# 3_BLE-T1-mcu.net
KiCad netlist of a schematic drawn in Altium Designer
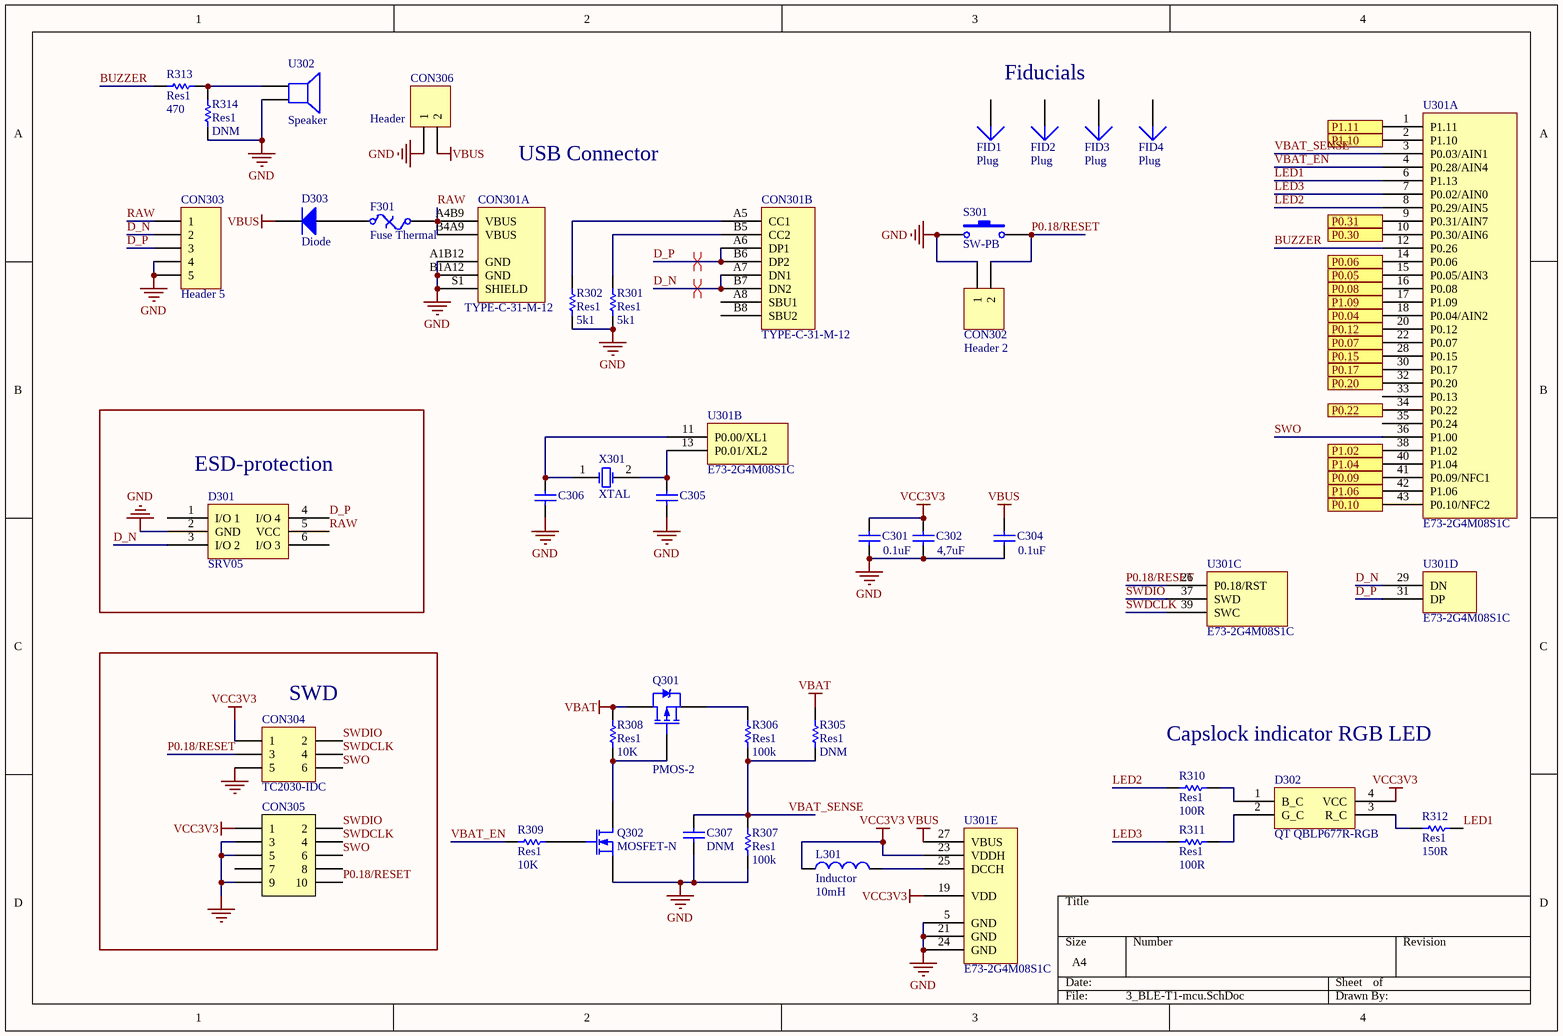
[diagram p0: 3_BLE-T1-mcu.SchDoc]

(export (version "E")
  (design (tool "Eeschema 10.0.6"))
  (components
    (comp (ref "C301")
      (value "0.1uF")
      (footprint "C0603[1608]")
      (description "Capacitor")
      (fields (field (name "MFG") "KEMET") (field (name "LCSC PART #") "C14663"))
      (libsource (lib "Miscellaneous Devices") (part "Cap"))
    )
    (comp (ref "C302")
      (value "4,7uF")
      (footprint "C0603[1608]")
      (description "Capacitor")
      (fields (field (name "LCSC PART #") "C19666") (field (name "MRF.PART") "CL10A475KO8NNNC"))
      (libsource (lib "Miscellaneous Devices") (part "Cap"))
    )
    (comp (ref "C304")
      (value "0.1uF")
      (footprint "C0603[1608]")
      (description "Capacitor")
      (fields (field (name "MFG") "KEMET") (field (name "LCSC PART #") "C14663"))
      (libsource (lib "Miscellaneous Devices") (part "Cap"))
    )
    (comp (ref "C305")
      (value "~")
      (footprint "C0603[1608]")
      (description "Capacitor")
      (libsource (lib "Miscellaneous Devices") (part "Cap"))
    )
    (comp (ref "C306")
      (value "~")
      (footprint "C0603[1608]")
      (description "Capacitor")
      (libsource (lib "Miscellaneous Devices") (part "Cap"))
    )
    (comp (ref "C307")
      (value "DNM")
      (footprint "C0603[1608]")
      (description "Capacitor")
      (libsource (lib "Miscellaneous Devices") (part "Cap"))
    )
    (comp (ref "CON301")
      (value "TYPE-C-31-M-12")
      (footprint "TYPE-C-31-M-12")
      (fields (field (name "MFG") "Korean Hroparts Elec") (field (name "LCSC PART #") "C165948"))
      (libsource (lib "Schlib1") (part "TYPE-C-31-M-12"))
    )
    (comp (ref "CON302")
      (value "Header 2")
      (footprint "HDR1X2")
      (description "Header, 2-Pin")
      (libsource (lib "") (part "Header 2_1"))
    )
    (comp (ref "CON303")
      (value "Header 5")
      (footprint "JST SM04B-SRSS-TB")
      (description "JST for USB daughter board")
      (fields (field (name "MFG") "JST Sales America Inc.") (field (name "LCSC PART #") "C160404"))
      (libsource (lib "Miscellaneous Connectors") (part "Header 5"))
    )
    (comp (ref "CON304")
      (value "TC2030-IDC")
      (footprint "TC2030-IDC-NL")
      (description "Header, 3-Pin, Dual row")
      (libsource (lib "Miscellaneous Connectors") (part "Header 3X2"))
    )
    (comp (ref "CON305")
      (value "~")
      (footprint "HDR_2x5-SMD-1.27mm-K")
      (description "Pin Header 2x5, 1.27mm (50mil), SMD, Keying Shroud")
      (fields (field (name "MFG") "Samtec Inc."))
      (libsource (lib "Nordic Passive DB") (part "CONN-2x5"))
    )
    (comp (ref "CON306")
      (value "Header")
      (footprint "HDR1X2")
      (description "Header, 2-Pin")
      (libsource (lib "Miscellaneous Connectors") (part "Header 2"))
    )
    (comp (ref "D301")
      (value "SRV05")
      (footprint "SOT-23-6")
      (fields (field (name "LCSC PART #") "C85364") (field (name "MRF.PART") "SRV05-4-P-T7"))
      (libsource (lib "Keebs") (part "SRV05"))
    )
    (comp (ref "D302")
      (value "QT QBLP677R-RGB")
      (footprint "QT QBLP677R-RGB")
      (description "RGB LED")
      (fields (field (name "MFG") "QT Brightek (QTB)"))
      (libsource (lib "Keebs") (part "QT QBLP677R-RGB"))
    )
    (comp (ref "D303")
      (value "Diode")
      (footprint "SOD-123")
      (description "Default Diode")
      (fields (field (name "LCSC PART #") "C8598") (field (name "MRF.PART") "B5819W"))
      (libsource (lib "Miscellaneous Devices") (part "Diode"))
    )
    (comp (ref "F301")
      (value "Fuse Thermal")
      (footprint "C1206[3216]")
      (description "Thermal Fuse")
      (fields (field (name "MFG") "Bel Fuse Inc.") (field (name "LCSC PART #") "C135338"))
      (libsource (lib "Miscellaneous Devices") (part "Fuse Thermal"))
    )
    (comp (ref "FID1")
      (value "Plug")
      (footprint "Fiducial_Nordic")
      (libsource (lib "Miscellaneous Connectors") (part "Plug"))
    )
    (comp (ref "FID2")
      (value "Plug")
      (footprint "Fiducial_Nordic")
      (libsource (lib "Miscellaneous Connectors") (part "Plug"))
    )
    (comp (ref "FID3")
      (value "Plug")
      (footprint "Fiducial_Nordic")
      (libsource (lib "Miscellaneous Connectors") (part "Plug"))
    )
    (comp (ref "FID4")
      (value "Plug")
      (footprint "Fiducial_Nordic")
      (libsource (lib "Miscellaneous Connectors") (part "Plug"))
    )
    (comp (ref "L301")
      (value "Inductor")
      (footprint "C0603[1608]")
      (fields (field (name "ALTIUM_VALUE") "10mH"))
      (libsource (lib "Miscellaneous Devices") (part "Inductor"))
    )
    (comp (ref "Q301")
      (value "PMOS-2")
      (footprint "SOT-23-3")
      (description "P-Channel Power MOSFET")
      (fields (field (name "MRF.PART") "SI2301CDS-T1-GE3") (field (name "LCSC PART #") "C10487"))
      (libsource (lib "Miscellaneous Devices") (part "PMOS-2"))
    )
    (comp (ref "Q302")
      (value "MOSFET-N")
      (footprint "SOT-23-3")
      (description "N-Channel MOSFET")
      (fields (field (name "LCSC PART #") "C8545") (field (name "MRF.PART") "2N7002"))
      (libsource (lib "Miscellaneous Devices") (part "MOSFET-N"))
    )
    (comp (ref "R301")
      (value "Res1")
      (footprint "R0603[1608]")
      (description "Resistor")
      (fields
        (field (name "ALTIUM_VALUE") "5k1")
        (field (name "LCSC PART #") "C23186")
        (field (name "MRF.PART") "0603WAF5101T5E")
      )
      (libsource (lib "Miscellaneous Devices") (part "Res1"))
    )
    (comp (ref "R302")
      (value "Res1")
      (footprint "R0603[1608]")
      (description "Resistor")
      (fields
        (field (name "ALTIUM_VALUE") "5k1")
        (field (name "LCSC PART #") "C23186")
        (field (name "MRF.PART") "0603WAF5101T5E")
      )
      (libsource (lib "Miscellaneous Devices") (part "Res1"))
    )
    (comp (ref "R305")
      (value "Res1")
      (footprint "R0603[1608]")
      (description "Resistor")
      (fields (field (name "ALTIUM_VALUE") "DNM"))
      (libsource (lib "Miscellaneous Devices") (part "Res1"))
    )
    (comp (ref "R306")
      (value "Res1")
      (footprint "R0603[1608]")
      (description "Resistor")
      (fields
        (field (name "ALTIUM_VALUE") "100k")
        (field (name "MRF.PART") "0603WAF1003T5E")
        (field (name "LCSC PART #") "C25803")
      )
      (libsource (lib "Miscellaneous Devices") (part "Res1"))
    )
    (comp (ref "R307")
      (value "Res1")
      (footprint "R0603[1608]")
      (description "Resistor")
      (fields
        (field (name "ALTIUM_VALUE") "100k")
        (field (name "MRF.PART") "0603WAF1003T5E")
        (field (name "LCSC PART #") "C25803")
      )
      (libsource (lib "Miscellaneous Devices") (part "Res1"))
    )
    (comp (ref "R308")
      (value "Res1")
      (footprint "R0603[1608]")
      (description "Resistor")
      (fields (field (name "ALTIUM_VALUE") "10K"))
      (libsource (lib "Miscellaneous Devices") (part "Res1"))
    )
    (comp (ref "R309")
      (value "Res1")
      (footprint "R0603[1608]")
      (description "Resistor")
      (fields (field (name "ALTIUM_VALUE") "10K"))
      (libsource (lib "Miscellaneous Devices") (part "Res1"))
    )
    (comp (ref "R310")
      (value "Res1")
      (footprint "R0603[1608]")
      (description "Resistor")
      (fields
        (field (name "ALTIUM_VALUE") "100R")
        (field (name "LCSC PART #") "C22775")
        (field (name "MRF.PART") "0603WAF1000T5E")
      )
      (libsource (lib "Miscellaneous Devices") (part "Res1"))
    )
    (comp (ref "R311")
      (value "Res1")
      (footprint "R0603[1608]")
      (description "Resistor")
      (fields
        (field (name "ALTIUM_VALUE") "100R")
        (field (name "LCSC PART #") "C22775")
        (field (name "MRF.PART") "0603WAF1000T5E")
      )
      (libsource (lib "Miscellaneous Devices") (part "Res1"))
    )
    (comp (ref "R312")
      (value "Res1")
      (footprint "R0603[1608]")
      (description "Resistor")
      (fields
        (field (name "ALTIUM_VALUE") "150R")
        (field (name "LCSC PART #") "C22808")
        (field (name "MRF.PART") "0603WAF1500T5E")
      )
      (libsource (lib "Miscellaneous Devices") (part "Res1"))
    )
    (comp (ref "R313")
      (value "Res1")
      (footprint "R0603[1608]")
      (description "Resistor")
      (fields
        (field (name "ALTIUM_VALUE") "470")
        (field (name "MFG") "Panasonic Electronic Components")
        (field (name "LCSC PART #") "C23179")
      )
      (libsource (lib "Miscellaneous Devices") (part "Res1"))
    )
    (comp (ref "R314")
      (value "Res1")
      (footprint "R0603[1608]")
      (description "Resistor")
      (fields
        (field (name "ALTIUM_VALUE") "DNM")
        (field (name "LCSC PART #") "C23345")
        (field (name "MRF.PART") "0603WAF220JT5E")
      )
      (libsource (lib "Miscellaneous Devices") (part "Res1"))
    )
    (comp (ref "S301")
      (value "SW-PB")
      (footprint "Combo switch")
      (description "Switch")
      (fields (field (name "MFG") "C&K") (field (name "MRF.PART") "TS-1187A-C-D-B"))
      (libsource (lib "Miscellaneous Devices") (part "SW-PB"))
    )
    (comp (ref "U301")
      (value "E73-2G4M08S1C")
      (footprint "E73-2G4M08S1C BLE-T1")
      (libsource (lib "Keebs") (part "E73-2G4M08S1C"))
    )
    (comp (ref "U302")
      (value "Speaker")
      (footprint "buzzer 12x12")
      (description "Loudspeaker")
      (libsource (lib "Miscellaneous Devices") (part "Speaker"))
    )
    (comp (ref "X301")
      (value "XTAL")
      (footprint "Seiko Epson Q13FC1350000400")
      (description "Crystal Oscillator")
      (fields (field (name "LCSC PART #") "C32346") (field (name "MRF.PART") "Q13FC1350000400"))
      (libsource (lib "Miscellaneous Devices") (part "XTAL"))
    )
  )
  (nets
    (net (code "1") (name "/BUZZER") (class "Default")
      (node (ref "R313") (pin "1") (pinfunction "1_1") (pintype "passive"))
      (node (ref "U301") (pin "12") (pinfunction "P0.26_12") (pintype "passive"))
    )
    (net (code "2") (name "/D_N") (class "Default")
      (node (ref "CON301") (pin "A7") (pinfunction "DN1_A7") (pintype "passive"))
      (node (ref "CON301") (pin "B7") (pinfunction "DN2_B7") (pintype "passive"))
      (node (ref "CON303") (pin "2") (pinfunction "2_2") (pintype "passive"))
      (node (ref "D301") (pin "3") (pinfunction "I/O_2_3") (pintype "passive"))
      (node (ref "U301") (pin "29") (pinfunction "DN_29") (pintype "passive"))
    )
    (net (code "3") (name "/D_P") (class "Default")
      (node (ref "CON301") (pin "A6") (pinfunction "DP1_A6") (pintype "passive"))
      (node (ref "CON301") (pin "B6") (pinfunction "DP2_B6") (pintype "passive"))
      (node (ref "CON303") (pin "3") (pinfunction "3_3") (pintype "passive"))
      (node (ref "D301") (pin "4") (pinfunction "I/O_4_4") (pintype "passive"))
      (node (ref "U301") (pin "31") (pinfunction "DP_31") (pintype "passive"))
    )
    (net (code "4") (name "/LED1") (class "Default")
      (node (ref "R312") (pin "1") (pinfunction "1_1") (pintype "passive"))
      (node (ref "U301") (pin "6") (pinfunction "P1.13_6") (pintype "passive"))
    )
    (net (code "5") (name "/LED2") (class "Default")
      (node (ref "R310") (pin "2") (pinfunction "2_2") (pintype "passive"))
      (node (ref "U301") (pin "8") (pinfunction "P0.29/AIN5_8") (pintype "passive"))
    )
    (net (code "6") (name "/LED3") (class "Default")
      (node (ref "R311") (pin "2") (pinfunction "2_2") (pintype "passive"))
      (node (ref "U301") (pin "7") (pinfunction "P0.02/AIN0_7") (pintype "passive"))
    )
    (net (code "7") (name "/P0.04") (class "Default")
      (node (ref "U301") (pin "18") (pinfunction "P0.04/AIN2_18") (pintype "passive"))
    )
    (net (code "8") (name "/P0.05") (class "Default")
      (node (ref "U301") (pin "15") (pinfunction "P0.05/AIN3_15") (pintype "passive"))
    )
    (net (code "9") (name "/P0.06") (class "Default")
      (node (ref "U301") (pin "14") (pinfunction "P0.06_14") (pintype "passive"))
    )
    (net (code "10") (name "/P0.07") (class "Default")
      (node (ref "U301") (pin "22") (pinfunction "P0.07_22") (pintype "passive"))
    )
    (net (code "11") (name "/P0.08") (class "Default")
      (node (ref "U301") (pin "16") (pinfunction "P0.08_16") (pintype "passive"))
    )
    (net (code "12") (name "/P0.09") (class "Default")
      (node (ref "U301") (pin "41") (pinfunction "P0.09/NFC1_41") (pintype "passive"))
    )
    (net (code "13") (name "/P0.10") (class "Default")
      (node (ref "U301") (pin "43") (pinfunction "P0.10/NFC2_43") (pintype "passive"))
    )
    (net (code "14") (name "/P0.12") (class "Default")
      (node (ref "U301") (pin "20") (pinfunction "P0.12_20") (pintype "passive"))
    )
    (net (code "15") (name "/P0.15") (class "Default")
      (node (ref "U301") (pin "28") (pinfunction "P0.15_28") (pintype "passive"))
    )
    (net (code "16") (name "/P0.17") (class "Default")
      (node (ref "U301") (pin "30") (pinfunction "P0.17_30") (pintype "passive"))
    )
    (net (code "17") (name "/P0.18{slash}RESET") (class "Default")
      (node (ref "CON302") (pin "2") (pinfunction "2_2") (pintype "passive"))
      (node (ref "CON304") (pin "3") (pinfunction "3_3") (pintype "passive"))
      (node (ref "CON305") (pin "10") (pinfunction "10_10") (pintype "passive"))
      (node (ref "S301") (pin "2") (pinfunction "2_2") (pintype "passive"))
      (node (ref "U301") (pin "26") (pinfunction "P0.18/RST_26") (pintype "passive"))
    )
    (net (code "18") (name "/P0.20") (class "Default")
      (node (ref "U301") (pin "32") (pinfunction "P0.20_32") (pintype "passive"))
    )
    (net (code "19") (name "/P0.22") (class "Default")
      (node (ref "U301") (pin "34") (pinfunction "P0.22_34") (pintype "passive"))
    )
    (net (code "20") (name "/P0.30") (class "Default")
      (node (ref "U301") (pin "10") (pinfunction "P0.30/AIN6_10") (pintype "passive"))
    )
    (net (code "21") (name "/P0.31") (class "Default")
      (node (ref "U301") (pin "9") (pinfunction "P0.31/AIN7_9") (pintype "passive"))
    )
    (net (code "22") (name "/P1.02") (class "Default")
      (node (ref "U301") (pin "38") (pinfunction "P1.02_38") (pintype "passive"))
    )
    (net (code "23") (name "/P1.04") (class "Default")
      (node (ref "U301") (pin "40") (pinfunction "P1.04_40") (pintype "passive"))
    )
    (net (code "24") (name "/P1.06") (class "Default")
      (node (ref "U301") (pin "42") (pinfunction "P1.06_42") (pintype "passive"))
    )
    (net (code "25") (name "/P1.09") (class "Default")
      (node (ref "U301") (pin "17") (pinfunction "P1.09_17") (pintype "passive"))
    )
    (net (code "26") (name "/P1.10") (class "Default")
      (node (ref "U301") (pin "2") (pinfunction "P1.10_2") (pintype "passive"))
    )
    (net (code "27") (name "/P1.11") (class "Default")
      (node (ref "U301") (pin "1") (pinfunction "P1.11_1") (pintype "passive"))
    )
    (net (code "28") (name "/RAW") (class "Default")
      (node (ref "CON301") (pin "A4B9") (pinfunction "VBUS_A4B9") (pintype "passive"))
      (node (ref "CON301") (pin "B4A9") (pinfunction "VBUS_B4A9") (pintype "passive"))
      (node (ref "CON303") (pin "1") (pinfunction "1_1") (pintype "passive"))
      (node (ref "D301") (pin "5") (pinfunction "VCC_5") (pintype "passive"))
      (node (ref "F301") (pin "2") (pinfunction "2_2") (pintype "passive"))
    )
    (net (code "29") (name "/SWDCLK") (class "Default")
      (node (ref "CON304") (pin "4") (pinfunction "4_4") (pintype "passive"))
      (node (ref "CON305") (pin "4") (pinfunction "4_4") (pintype "passive"))
      (node (ref "U301") (pin "39") (pinfunction "SWC_39") (pintype "passive"))
    )
    (net (code "30") (name "/SWDIO") (class "Default")
      (node (ref "CON304") (pin "2") (pinfunction "2_2") (pintype "passive"))
      (node (ref "CON305") (pin "2") (pinfunction "2_2") (pintype "passive"))
      (node (ref "U301") (pin "37") (pinfunction "SWD_37") (pintype "passive"))
    )
    (net (code "31") (name "/SWO") (class "Default")
      (node (ref "CON304") (pin "6") (pinfunction "6_6") (pintype "passive"))
      (node (ref "CON305") (pin "6") (pinfunction "6_6") (pintype "passive"))
      (node (ref "U301") (pin "36") (pinfunction "P1.00_36") (pintype "passive"))
    )
    (net (code "32") (name "/VBAT_EN") (class "Default")
      (node (ref "R309") (pin "2") (pinfunction "2_2") (pintype "passive"))
      (node (ref "U301") (pin "4") (pinfunction "P0.28/AIN4_4") (pintype "passive"))
    )
    (net (code "33") (name "/VBAT_SENSE") (class "Default")
      (node (ref "C307") (pin "2") (pinfunction "2_2") (pintype "passive"))
      (node (ref "R305") (pin "1") (pinfunction "1_1") (pintype "passive"))
      (node (ref "R306") (pin "2") (pinfunction "2_2") (pintype "passive"))
      (node (ref "R307") (pin "1") (pinfunction "1_1") (pintype "passive"))
      (node (ref "U301") (pin "3") (pinfunction "P0.03/AIN1_3") (pintype "passive"))
    )
    (net (code "34") (name "GND") (class "Default")
      (node (ref "C301") (pin "1") (pinfunction "1_1") (pintype "passive"))
      (node (ref "C302") (pin "1") (pinfunction "1_1") (pintype "passive"))
      (node (ref "C304") (pin "1") (pinfunction "1_1") (pintype "passive"))
      (node (ref "C305") (pin "1") (pinfunction "1_1") (pintype "passive"))
      (node (ref "C306") (pin "1") (pinfunction "1_1") (pintype "passive"))
      (node (ref "C307") (pin "1") (pinfunction "1_1") (pintype "passive"))
      (node (ref "CON301") (pin "A1B12") (pinfunction "GND_A1B12") (pintype "passive"))
      (node (ref "CON301") (pin "B1A12") (pinfunction "GND_B1A12") (pintype "passive"))
      (node (ref "CON301") (pin "S1") (pinfunction "SHIELD_S1") (pintype "passive"))
      (node (ref "CON302") (pin "1") (pinfunction "1_1") (pintype "passive"))
      (node (ref "CON303") (pin "4") (pinfunction "4_4") (pintype "passive"))
      (node (ref "CON303") (pin "5") (pinfunction "5_5") (pintype "passive"))
      (node (ref "CON304") (pin "5") (pinfunction "5_5") (pintype "passive"))
      (node (ref "CON305") (pin "3") (pinfunction "3_3") (pintype "passive"))
      (node (ref "CON305") (pin "5") (pinfunction "5_5") (pintype "passive"))
      (node (ref "CON305") (pin "9") (pinfunction "9_9") (pintype "passive"))
      (node (ref "CON306") (pin "1") (pinfunction "1_1") (pintype "passive"))
      (node (ref "D301") (pin "2") (pinfunction "GND_2") (pintype "passive"))
      (node (ref "Q302") (pin "2") (pinfunction "S_2") (pintype "passive"))
      (node (ref "R301") (pin "2") (pinfunction "2_2") (pintype "passive"))
      (node (ref "R302") (pin "2") (pinfunction "2_2") (pintype "passive"))
      (node (ref "R307") (pin "2") (pinfunction "2_2") (pintype "passive"))
      (node (ref "R314") (pin "1") (pinfunction "1_1") (pintype "passive"))
      (node (ref "S301") (pin "1") (pinfunction "1_1") (pintype "passive"))
      (node (ref "U301") (pin "21") (pinfunction "GND_21") (pintype "passive"))
      (node (ref "U301") (pin "24") (pinfunction "GND_24") (pintype "passive"))
      (node (ref "U301") (pin "5") (pinfunction "GND_5") (pintype "passive"))
      (node (ref "U302") (pin "2") (pinfunction "2_2") (pintype "passive"))
    )
    (net (code "35") (name "Net-(CON301B-CC1)") (class "Default")
      (node (ref "CON301") (pin "A5") (pinfunction "CC1_A5") (pintype "passive"))
      (node (ref "R302") (pin "1") (pinfunction "1_1") (pintype "passive"))
    )
    (net (code "36") (name "Net-(CON301B-CC2)") (class "Default")
      (node (ref "CON301") (pin "B5") (pinfunction "CC2_B5") (pintype "passive"))
      (node (ref "R301") (pin "1") (pinfunction "1_1") (pintype "passive"))
    )
    (net (code "37") (name "Net-(D302-B_C)") (class "Default")
      (node (ref "D302") (pin "1") (pinfunction "B_C_1") (pintype "passive"))
      (node (ref "R310") (pin "1") (pinfunction "1_1") (pintype "passive"))
    )
    (net (code "38") (name "Net-(D302-G_C)") (class "Default")
      (node (ref "D302") (pin "2") (pinfunction "G_C_2") (pintype "passive"))
      (node (ref "R311") (pin "1") (pinfunction "1_1") (pintype "passive"))
    )
    (net (code "39") (name "Net-(D302-R_C)") (class "Default")
      (node (ref "D302") (pin "3") (pinfunction "R_C_3") (pintype "passive"))
      (node (ref "R312") (pin "2") (pinfunction "2_2") (pintype "passive"))
    )
    (net (code "40") (name "Net-(D303-A)") (class "Default")
      (node (ref "D303") (pin "1") (pinfunction "A_1") (pintype "passive"))
      (node (ref "F301") (pin "1") (pinfunction "1_1") (pintype "passive"))
    )
    (net (code "41") (name "Net-(Q301-G)") (class "Default")
      (node (ref "Q301") (pin "1") (pinfunction "G_1") (pintype "passive"))
      (node (ref "Q302") (pin "3") (pinfunction "D_3") (pintype "passive"))
      (node (ref "R308") (pin "1") (pinfunction "1_1") (pintype "passive"))
    )
    (net (code "42") (name "Net-(Q301-S)") (class "Default")
      (node (ref "Q301") (pin "2") (pinfunction "S_2") (pintype "passive"))
      (node (ref "R306") (pin "1") (pinfunction "1_1") (pintype "passive"))
    )
    (net (code "43") (name "Net-(Q302-G)") (class "Default")
      (node (ref "Q302") (pin "1") (pinfunction "G_1") (pintype "passive"))
      (node (ref "R309") (pin "1") (pinfunction "1_1") (pintype "passive"))
    )
    (net (code "44") (name "Net-(R313-Pad2)") (class "Default")
      (node (ref "R313") (pin "2") (pinfunction "2_2") (pintype "passive"))
      (node (ref "R314") (pin "2") (pinfunction "2_2") (pintype "passive"))
      (node (ref "U302") (pin "1") (pinfunction "1_1") (pintype "passive"))
    )
    (net (code "45") (name "Net-(U301B-P0.00{slash}XL1)") (class "Default")
      (node (ref "C306") (pin "2") (pinfunction "2_2") (pintype "passive"))
      (node (ref "U301") (pin "11") (pinfunction "P0.00/XL1_11") (pintype "passive"))
      (node (ref "X301") (pin "1") (pinfunction "OSC1_1") (pintype "passive"))
    )
    (net (code "46") (name "Net-(U301B-P0.01{slash}XL2)") (class "Default")
      (node (ref "C305") (pin "2") (pinfunction "2_2") (pintype "passive"))
      (node (ref "U301") (pin "13") (pinfunction "P0.01/XL2_13") (pintype "passive"))
      (node (ref "X301") (pin "2") (pinfunction "OSC2_2") (pintype "passive"))
    )
    (net (code "47") (name "Net-(U301E-DCCH)") (class "Default")
      (node (ref "L301") (pin "2") (pinfunction "2_2") (pintype "passive"))
      (node (ref "U301") (pin "25") (pinfunction "DCCH_25") (pintype "passive"))
    )
    (net (code "48") (name "VBAT") (class "Default")
      (node (ref "Q301") (pin "3") (pinfunction "D_3") (pintype "passive"))
      (node (ref "R305") (pin "2") (pinfunction "2_2") (pintype "passive"))
      (node (ref "R308") (pin "2") (pinfunction "2_2") (pintype "passive"))
    )
    (net (code "49") (name "VBUS") (class "Default")
      (node (ref "C304") (pin "2") (pinfunction "2_2") (pintype "passive"))
      (node (ref "CON306") (pin "2") (pinfunction "2_2") (pintype "passive"))
      (node (ref "D303") (pin "2") (pinfunction "K_2") (pintype "passive"))
      (node (ref "U301") (pin "27") (pinfunction "VBUS_27") (pintype "passive"))
    )
    (net (code "50") (name "VCC3V3") (class "Default")
      (node (ref "C301") (pin "2") (pinfunction "2_2") (pintype "passive"))
      (node (ref "C302") (pin "2") (pinfunction "2_2") (pintype "passive"))
      (node (ref "CON304") (pin "1") (pinfunction "1_1") (pintype "passive"))
      (node (ref "CON305") (pin "1") (pinfunction "1_1") (pintype "passive"))
      (node (ref "D302") (pin "4") (pinfunction "VCC_4") (pintype "passive"))
      (node (ref "L301") (pin "1") (pinfunction "1_1") (pintype "passive"))
      (node (ref "U301") (pin "19") (pinfunction "VDD_19") (pintype "passive"))
      (node (ref "U301") (pin "23") (pinfunction "VDDH_23") (pintype "passive"))
    )
    (net (code "51") (name "unconnected-(CON301B-SBU1-PadA8)") (class "Default")
      (node (ref "CON301") (pin "A8") (pinfunction "SBU1_A8") (pintype "passive"))
    )
    (net (code "52") (name "unconnected-(CON301B-SBU2-PadB8)") (class "Default")
      (node (ref "CON301") (pin "B8") (pinfunction "SBU2_B8") (pintype "passive"))
    )
    (net (code "53") (name "unconnected-(CON305-Pad7)") (class "Default")
      (node (ref "CON305") (pin "7") (pinfunction "7_7") (pintype "passive"))
    )
    (net (code "54") (name "unconnected-(CON305-Pad8)") (class "Default")
      (node (ref "CON305") (pin "8") (pinfunction "8_8") (pintype "passive"))
    )
    (net (code "55") (name "unconnected-(D301-I{slash}O_1-Pad1)") (class "Default")
      (node (ref "D301") (pin "1") (pinfunction "I/O_1_1") (pintype "passive"))
    )
    (net (code "56") (name "unconnected-(D301-I{slash}O_3-Pad6)") (class "Default")
      (node (ref "D301") (pin "6") (pinfunction "I/O_3_6") (pintype "passive"))
    )
    (net (code "57") (name "unconnected-(FID1-Pad1)") (class "Default")
      (node (ref "FID1") (pin "1") (pinfunction "1_1") (pintype "passive"))
    )
    (net (code "58") (name "unconnected-(FID2-Pad1)") (class "Default")
      (node (ref "FID2") (pin "1") (pinfunction "1_1") (pintype "passive"))
    )
    (net (code "59") (name "unconnected-(FID3-Pad1)") (class "Default")
      (node (ref "FID3") (pin "1") (pinfunction "1_1") (pintype "passive"))
    )
    (net (code "60") (name "unconnected-(FID4-Pad1)") (class "Default")
      (node (ref "FID4") (pin "1") (pinfunction "1_1") (pintype "passive"))
    )
    (net (code "61") (name "unconnected-(U301A-P0.13-Pad33)") (class "Default")
      (node (ref "U301") (pin "33") (pinfunction "P0.13_33") (pintype "passive"))
    )
    (net (code "62") (name "unconnected-(U301A-P0.24-Pad35)") (class "Default")
      (node (ref "U301") (pin "35") (pinfunction "P0.24_35") (pintype "passive"))
    )
  )
)
